# 5v-esp8266-switch-sensor.net
KiCad netlist of a schematic drawn in EAGLE
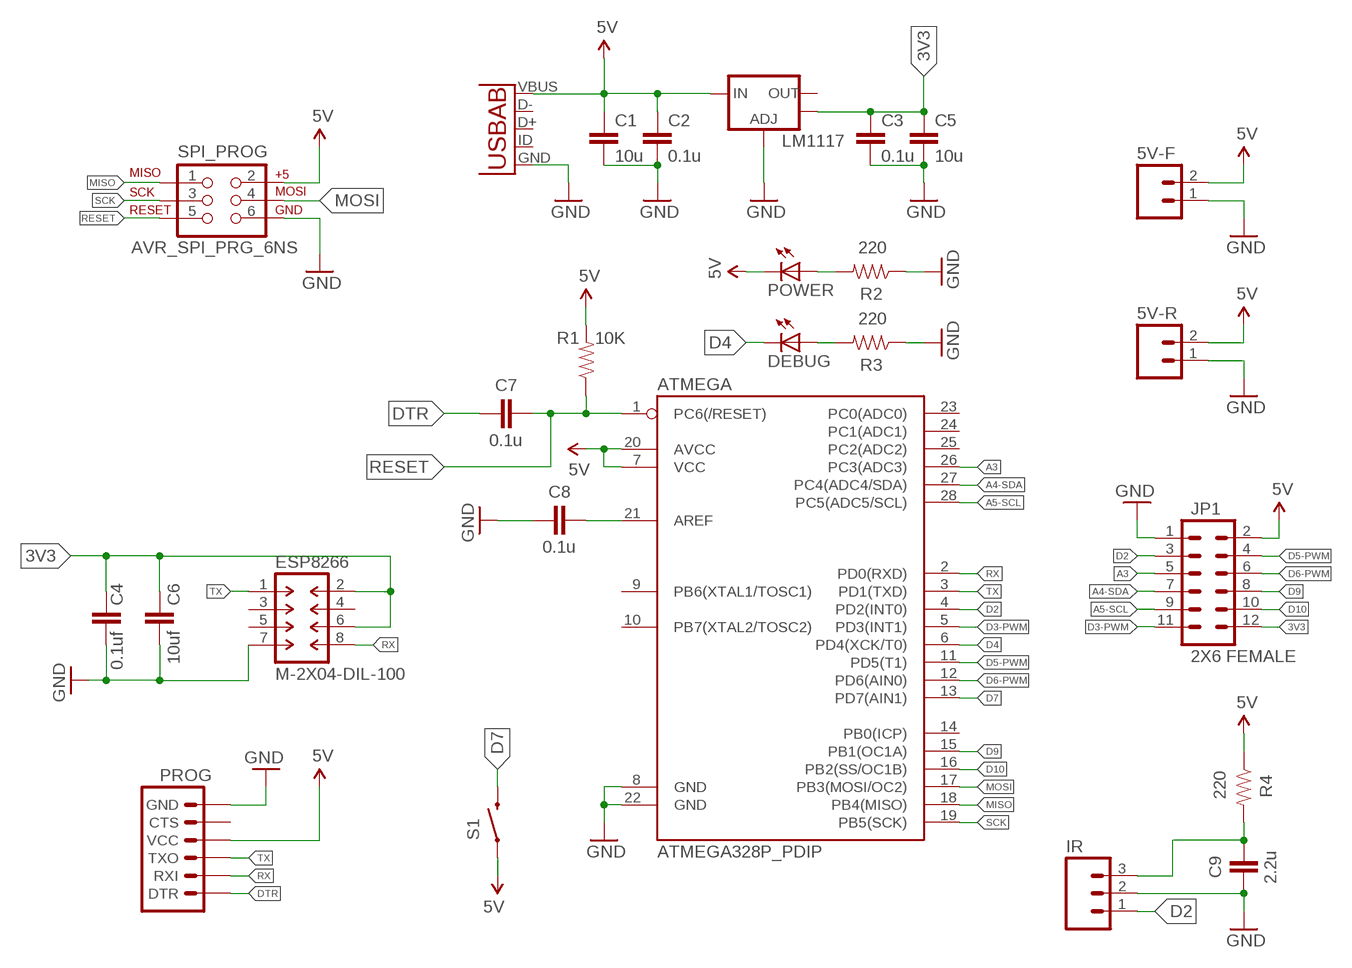
[diagram p0: schematic, sheet 1]

(export (version "E")
  (design (tool "Eeschema 10.0.6"))
  (components
    (comp (ref "5V-F")
      (value "M02PTH")
      (footprint "eagle-import:1X02")
      (libsource (lib "eagle-import") (part "M02PTH"))
    )
    (comp (ref "5V-R")
      (value "M02PTH")
      (footprint "eagle-import:1X02")
      (libsource (lib "eagle-import") (part "M02PTH"))
    )
    (comp (ref "ATMEGA")
      (value "ATMEGA328P_PDIP")
      (footprint "eagle-import:DIL28-3")
      (libsource (lib "eagle-import") (part "ATMEGA328P_PDIP"))
    )
    (comp (ref "C1")
      (value "10u")
      (footprint "eagle-import:0805")
      (libsource (lib "eagle-import") (part "CAP0805"))
    )
    (comp (ref "C2")
      (value "0.1u")
      (footprint "eagle-import:0805")
      (libsource (lib "eagle-import") (part "CAP0805"))
    )
    (comp (ref "C3")
      (value "0.1u")
      (footprint "eagle-import:0805")
      (libsource (lib "eagle-import") (part "CAP0805"))
    )
    (comp (ref "C4")
      (value "0.1uf")
      (footprint "eagle-import:0805")
      (libsource (lib "eagle-import") (part "CAP0805"))
    )
    (comp (ref "C5")
      (value "10u")
      (footprint "eagle-import:0805")
      (libsource (lib "eagle-import") (part "CAP0805"))
    )
    (comp (ref "C6")
      (value "10uf")
      (footprint "eagle-import:0805")
      (libsource (lib "eagle-import") (part "CAP0805"))
    )
    (comp (ref "C7")
      (value "0.1u")
      (footprint "eagle-import:0805")
      (libsource (lib "eagle-import") (part "CAP0805"))
    )
    (comp (ref "C8")
      (value "0.1u")
      (footprint "eagle-import:0805")
      (libsource (lib "eagle-import") (part "CAP0805"))
    )
    (comp (ref "C9")
      (value "2.2u")
      (footprint "eagle-import:0805")
      (libsource (lib "eagle-import") (part "CAP0805"))
    )
    (comp (ref "DEBUG")
      (value "LEDCHIPLED_0805")
      (footprint "eagle-import:CHIPLED_0805")
      (libsource (lib "eagle-import") (part "LEDCHIPLED_0805"))
    )
    (comp (ref "ESP8266")
      (value "M-2X04-DIL-100")
      (footprint "eagle-import:DIL-100-2X04")
      (libsource (lib "eagle-import") (part "M-2X04-DIL-100"))
    )
    (comp (ref "IR")
      (value "M03PTH")
      (footprint "eagle-import:1X03")
      (libsource (lib "eagle-import") (part "M03PTH"))
    )
    (comp (ref "JP1")
      (value "2X6 FEMALE")
      (footprint "eagle-import:2X6")
      (libsource (lib "eagle-import") (part "M06X2PTH_FEMALE"))
    )
    (comp (ref "LM1117")
      (value "V_REG_LM1117SOT223")
      (footprint "eagle-import:SOT223")
      (libsource (lib "eagle-import") (part "V_REG_LM1117SOT223"))
    )
    (comp (ref "POWER")
      (value "LEDCHIPLED_0805")
      (footprint "eagle-import:CHIPLED_0805")
      (libsource (lib "eagle-import") (part "LEDCHIPLED_0805"))
    )
    (comp (ref "PROG")
      (value "ARDUINO_SERIAL_PROGRAMPTH")
      (footprint "eagle-import:1X06")
      (libsource (lib "eagle-import") (part "ARDUINO_SERIAL_PROGRAMPTH"))
    )
    (comp (ref "R1")
      (value "10K")
      (footprint "eagle-import:0805")
      (libsource (lib "eagle-import") (part "RESISTOR0805-RES"))
    )
    (comp (ref "R2")
      (value "220")
      (footprint "eagle-import:0805")
      (libsource (lib "eagle-import") (part "RESISTOR0805-RES"))
    )
    (comp (ref "R3")
      (value "220")
      (footprint "eagle-import:0805")
      (libsource (lib "eagle-import") (part "RESISTOR0805-RES"))
    )
    (comp (ref "R4")
      (value "220")
      (footprint "eagle-import:0805")
      (libsource (lib "eagle-import") (part "RESISTOR0805-RES"))
    )
    (comp (ref "S1")
      (value "SWITCH-MOMENTARY-2SMD-1101NE")
      (footprint "eagle-import:TACTILE-SWITCH-1101NE")
      (libsource (lib "eagle-import") (part "SWITCH-MOMENTARY-2SMD-1101NE"))
    )
    (comp (ref "SPI_PROG")
      (value "AVR_SPI_PRG_6NS")
      (footprint "eagle-import:2X3-NS")
      (libsource (lib "eagle-import") (part "AVR_SPI_PRG_6NS"))
    )
    (comp (ref "U1")
      (value "USB-AB")
      (footprint "eagle-import:USB-AB-MICRO-SMD")
      (libsource (lib "eagle-import") (part "USB-AB"))
    )
  )
  (nets
    (net (code "1") (name "3V3") (class "Default")
      (node (ref "C3") (pin "1") (pinfunction "1_1") (pintype "passive"))
      (node (ref "C4") (pin "1") (pinfunction "1_1") (pintype "passive"))
      (node (ref "C5") (pin "1") (pinfunction "1_1") (pintype "passive"))
      (node (ref "C6") (pin "1") (pinfunction "1_1") (pintype "passive"))
      (node (ref "ESP8266") (pin "2") (pinfunction "2_2") (pintype "passive"))
      (node (ref "ESP8266") (pin "6") (pinfunction "6_6") (pintype "passive"))
      (node (ref "JP1") (pin "12") (pinfunction "12_12") (pintype "passive"))
      (node (ref "LM1117") (pin "4") (pinfunction "OUT_4") (pintype "output"))
    )
    (net (code "2") (name "5V") (class "Default")
      (node (ref "5V-F") (pin "2") (pinfunction "2_2") (pintype "passive"))
      (node (ref "5V-R") (pin "2") (pinfunction "2_2") (pintype "passive"))
      (node (ref "ATMEGA") (pin "20") (pinfunction "AVCC_20") (pintype "bidirectional"))
      (node (ref "ATMEGA") (pin "7") (pinfunction "VCC_7") (pintype "bidirectional"))
      (node (ref "C1") (pin "1") (pinfunction "1_1") (pintype "passive"))
      (node (ref "C2") (pin "1") (pinfunction "1_1") (pintype "passive"))
      (node (ref "JP1") (pin "2") (pinfunction "2_2") (pintype "passive"))
      (node (ref "LM1117") (pin "3") (pinfunction "IN_3") (pintype "input"))
      (node (ref "POWER") (pin "C") (pinfunction "C_C") (pintype "passive"))
      (node (ref "PROG") (pin "4") (pinfunction "VCC_4") (pintype "passive"))
      (node (ref "R1") (pin "2") (pinfunction "2_2") (pintype "passive"))
      (node (ref "R4") (pin "1") (pinfunction "1_1") (pintype "passive"))
      (node (ref "S1") (pin "1") (pinfunction "1_1") (pintype "passive"))
      (node (ref "SPI_PROG") (pin "2") (pinfunction "2_2") (pintype "passive"))
      (node (ref "U1") (pin "VBUS") (pinfunction "VBUS_VBUS") (pintype "bidirectional"))
    )
    (net (code "3") (name "A3") (class "Default")
      (node (ref "ATMEGA") (pin "26") (pinfunction "PC3(ADC3)_26") (pintype "bidirectional"))
      (node (ref "JP1") (pin "5") (pinfunction "5_5") (pintype "passive"))
    )
    (net (code "4") (name "A4-SDA") (class "Default")
      (node (ref "ATMEGA") (pin "27") (pinfunction "PC4(ADC4/SDA)_27") (pintype "bidirectional"))
      (node (ref "JP1") (pin "7") (pinfunction "7_7") (pintype "passive"))
    )
    (net (code "5") (name "A5-SCL") (class "Default")
      (node (ref "ATMEGA") (pin "28") (pinfunction "PC5(ADC5/SCL)_28") (pintype "bidirectional"))
      (node (ref "JP1") (pin "9") (pinfunction "9_9") (pintype "passive"))
    )
    (net (code "6") (name "D2") (class "Default")
      (node (ref "ATMEGA") (pin "4") (pinfunction "PD2(INT0)_4") (pintype "bidirectional"))
      (node (ref "IR") (pin "1") (pinfunction "1_1") (pintype "passive"))
      (node (ref "JP1") (pin "3") (pinfunction "3_3") (pintype "passive"))
    )
    (net (code "7") (name "D3-PWM") (class "Default")
      (node (ref "ATMEGA") (pin "5") (pinfunction "PD3(INT1)_5") (pintype "bidirectional"))
      (node (ref "JP1") (pin "11") (pinfunction "11_11") (pintype "passive"))
    )
    (net (code "8") (name "D4") (class "Default")
      (node (ref "ATMEGA") (pin "6") (pinfunction "PD4(XCK/T0)_6") (pintype "bidirectional"))
      (node (ref "DEBUG") (pin "C") (pinfunction "C_C") (pintype "passive"))
    )
    (net (code "9") (name "D5-PWM") (class "Default")
      (node (ref "ATMEGA") (pin "11") (pinfunction "PD5(T1)_11") (pintype "bidirectional"))
      (node (ref "JP1") (pin "4") (pinfunction "4_4") (pintype "passive"))
    )
    (net (code "10") (name "D6-PWM") (class "Default")
      (node (ref "ATMEGA") (pin "12") (pinfunction "PD6(AIN0)_12") (pintype "bidirectional"))
      (node (ref "JP1") (pin "6") (pinfunction "6_6") (pintype "passive"))
    )
    (net (code "11") (name "D7") (class "Default")
      (node (ref "ATMEGA") (pin "13") (pinfunction "PD7(AIN1)_13") (pintype "bidirectional"))
      (node (ref "S1") (pin "2") (pinfunction "2_2") (pintype "passive"))
    )
    (net (code "12") (name "D9") (class "Default")
      (node (ref "ATMEGA") (pin "15") (pinfunction "PB1(OC1A)_15") (pintype "bidirectional"))
      (node (ref "JP1") (pin "8") (pinfunction "8_8") (pintype "passive"))
    )
    (net (code "13") (name "D10") (class "Default")
      (node (ref "ATMEGA") (pin "16") (pinfunction "PB2(SS/OC1B)_16") (pintype "bidirectional"))
      (node (ref "JP1") (pin "10") (pinfunction "10_10") (pintype "passive"))
    )
    (net (code "14") (name "DTR") (class "Default")
      (node (ref "C7") (pin "1") (pinfunction "1_1") (pintype "passive"))
      (node (ref "PROG") (pin "1") (pinfunction "DTR_1") (pintype "passive"))
    )
    (net (code "15") (name "GND") (class "Default")
      (node (ref "5V-F") (pin "1") (pinfunction "1_1") (pintype "passive"))
      (node (ref "5V-R") (pin "1") (pinfunction "1_1") (pintype "passive"))
      (node (ref "ATMEGA") (pin "22") (pinfunction "GND_22") (pintype "bidirectional"))
      (node (ref "ATMEGA") (pin "8") (pinfunction "GND_8") (pintype "bidirectional"))
      (node (ref "C1") (pin "2") (pinfunction "2_2") (pintype "passive"))
      (node (ref "C2") (pin "2") (pinfunction "2_2") (pintype "passive"))
      (node (ref "C3") (pin "2") (pinfunction "2_2") (pintype "passive"))
      (node (ref "C4") (pin "2") (pinfunction "2_2") (pintype "passive"))
      (node (ref "C5") (pin "2") (pinfunction "2_2") (pintype "passive"))
      (node (ref "C6") (pin "2") (pinfunction "2_2") (pintype "passive"))
      (node (ref "C8") (pin "1") (pinfunction "1_1") (pintype "passive"))
      (node (ref "C9") (pin "1") (pinfunction "1_1") (pintype "passive"))
      (node (ref "ESP8266") (pin "7") (pinfunction "7_7") (pintype "passive"))
      (node (ref "IR") (pin "2") (pinfunction "2_2") (pintype "passive"))
      (node (ref "JP1") (pin "1") (pinfunction "1_1") (pintype "passive"))
      (node (ref "LM1117") (pin "1") (pinfunction "ADJ_1") (pintype "input"))
      (node (ref "PROG") (pin "6") (pinfunction "GND_6") (pintype "passive"))
      (node (ref "R2") (pin "1") (pinfunction "1_1") (pintype "passive"))
      (node (ref "R3") (pin "1") (pinfunction "1_1") (pintype "passive"))
      (node (ref "SPI_PROG") (pin "6") (pinfunction "6_6") (pintype "passive"))
      (node (ref "U1") (pin "GND") (pinfunction "GND_GND") (pintype "bidirectional"))
    )
    (net (code "16") (name "MISO") (class "Default")
      (node (ref "ATMEGA") (pin "18") (pinfunction "PB4(MISO)_18") (pintype "bidirectional"))
      (node (ref "SPI_PROG") (pin "1") (pinfunction "1_1") (pintype "passive"))
    )
    (net (code "17") (name "MOSI") (class "Default")
      (node (ref "ATMEGA") (pin "17") (pinfunction "PB3(MOSI/OC2)_17") (pintype "bidirectional"))
      (node (ref "SPI_PROG") (pin "4") (pinfunction "4_4") (pintype "passive"))
    )
    (net (code "18") (name "Net-(ATMEGA-AREF)") (class "Default")
      (node (ref "ATMEGA") (pin "21") (pinfunction "AREF_21") (pintype "bidirectional"))
      (node (ref "C8") (pin "2") (pinfunction "2_2") (pintype "passive"))
    )
    (net (code "19") (name "Net-(C9-Pad2)") (class "Default")
      (node (ref "C9") (pin "2") (pinfunction "2_2") (pintype "passive"))
      (node (ref "IR") (pin "3") (pinfunction "3_3") (pintype "passive"))
      (node (ref "R4") (pin "2") (pinfunction "2_2") (pintype "passive"))
    )
    (net (code "20") (name "Net-(DEBUG-PadA)") (class "Default")
      (node (ref "DEBUG") (pin "A") (pinfunction "A_A") (pintype "passive"))
      (node (ref "R3") (pin "2") (pinfunction "2_2") (pintype "passive"))
    )
    (net (code "21") (name "Net-(POWER-PadA)") (class "Default")
      (node (ref "POWER") (pin "A") (pinfunction "A_A") (pintype "passive"))
      (node (ref "R2") (pin "2") (pinfunction "2_2") (pintype "passive"))
    )
    (net (code "22") (name "RESET") (class "Default")
      (node (ref "ATMEGA") (pin "1") (pinfunction "PC6(/RESET)_1") (pintype "bidirectional"))
      (node (ref "C7") (pin "2") (pinfunction "2_2") (pintype "passive"))
      (node (ref "R1") (pin "1") (pinfunction "1_1") (pintype "passive"))
      (node (ref "SPI_PROG") (pin "5") (pinfunction "5_5") (pintype "passive"))
    )
    (net (code "23") (name "RX") (class "Default")
      (node (ref "ATMEGA") (pin "2") (pinfunction "PD0(RXD)_2") (pintype "bidirectional"))
      (node (ref "ESP8266") (pin "8") (pinfunction "8_8") (pintype "passive"))
      (node (ref "PROG") (pin "2") (pinfunction "RXI_2") (pintype "passive"))
    )
    (net (code "24") (name "SCK") (class "Default")
      (node (ref "ATMEGA") (pin "19") (pinfunction "PB5(SCK)_19") (pintype "bidirectional"))
      (node (ref "SPI_PROG") (pin "3") (pinfunction "3_3") (pintype "passive"))
    )
    (net (code "25") (name "TX") (class "Default")
      (node (ref "ATMEGA") (pin "3") (pinfunction "PD1(TXD)_3") (pintype "bidirectional"))
      (node (ref "ESP8266") (pin "1") (pinfunction "1_1") (pintype "passive"))
      (node (ref "PROG") (pin "3") (pinfunction "TXO_3") (pintype "passive"))
    )
    (net (code "26") (name "unconnected-(ATMEGA-PB0(ICP)-Pad14)") (class "Default")
      (node (ref "ATMEGA") (pin "14") (pinfunction "PB0(ICP)_14") (pintype "bidirectional"))
    )
    (net (code "27") (name "unconnected-(ATMEGA-PB6(XTAL1{slash}TOSC1)-Pad9)") (class "Default")
      (node (ref "ATMEGA") (pin "9") (pinfunction "PB6(XTAL1/TOSC1)_9") (pintype "bidirectional"))
    )
    (net (code "28") (name "unconnected-(ATMEGA-PB7(XTAL2{slash}TOSC2)-Pad10)") (class "Default")
      (node (ref "ATMEGA") (pin "10") (pinfunction "PB7(XTAL2/TOSC2)_10") (pintype "bidirectional"))
    )
    (net (code "29") (name "unconnected-(ATMEGA-PC0(ADC0)-Pad23)") (class "Default")
      (node (ref "ATMEGA") (pin "23") (pinfunction "PC0(ADC0)_23") (pintype "bidirectional"))
    )
    (net (code "30") (name "unconnected-(ATMEGA-PC1(ADC1)-Pad24)") (class "Default")
      (node (ref "ATMEGA") (pin "24") (pinfunction "PC1(ADC1)_24") (pintype "bidirectional"))
    )
    (net (code "31") (name "unconnected-(ATMEGA-PC2(ADC2)-Pad25)") (class "Default")
      (node (ref "ATMEGA") (pin "25") (pinfunction "PC2(ADC2)_25") (pintype "bidirectional"))
    )
    (net (code "32") (name "unconnected-(ESP8266-Pad3)") (class "Default")
      (node (ref "ESP8266") (pin "3") (pinfunction "3_3") (pintype "passive"))
    )
    (net (code "33") (name "unconnected-(ESP8266-Pad4)") (class "Default")
      (node (ref "ESP8266") (pin "4") (pinfunction "4_4") (pintype "passive"))
    )
    (net (code "34") (name "unconnected-(ESP8266-Pad5)") (class "Default")
      (node (ref "ESP8266") (pin "5") (pinfunction "5_5") (pintype "passive"))
    )
    (net (code "35") (name "unconnected-(LM1117-OUT-Pad2)") (class "Default")
      (node (ref "LM1117") (pin "2") (pinfunction "OUT_2") (pintype "output"))
    )
    (net (code "36") (name "unconnected-(PROG-CTS-Pad5)") (class "Default")
      (node (ref "PROG") (pin "5") (pinfunction "CTS_5") (pintype "passive"))
    )
    (net (code "37") (name "unconnected-(U1-PadD+)") (class "Default")
      (node (ref "U1") (pin "D+") (pinfunction "D+_D+") (pintype "bidirectional"))
    )
    (net (code "38") (name "unconnected-(U1-PadD-)") (class "Default")
      (node (ref "U1") (pin "D-") (pinfunction "D-_D-") (pintype "bidirectional"))
    )
    (net (code "39") (name "unconnected-(U1-USBID-PadID)") (class "Default")
      (node (ref "U1") (pin "ID") (pinfunction "USBID_ID") (pintype "bidirectional"))
    )
  )
)
